# Controller.net
KiCad netlist of a schematic drawn in Altium Designer
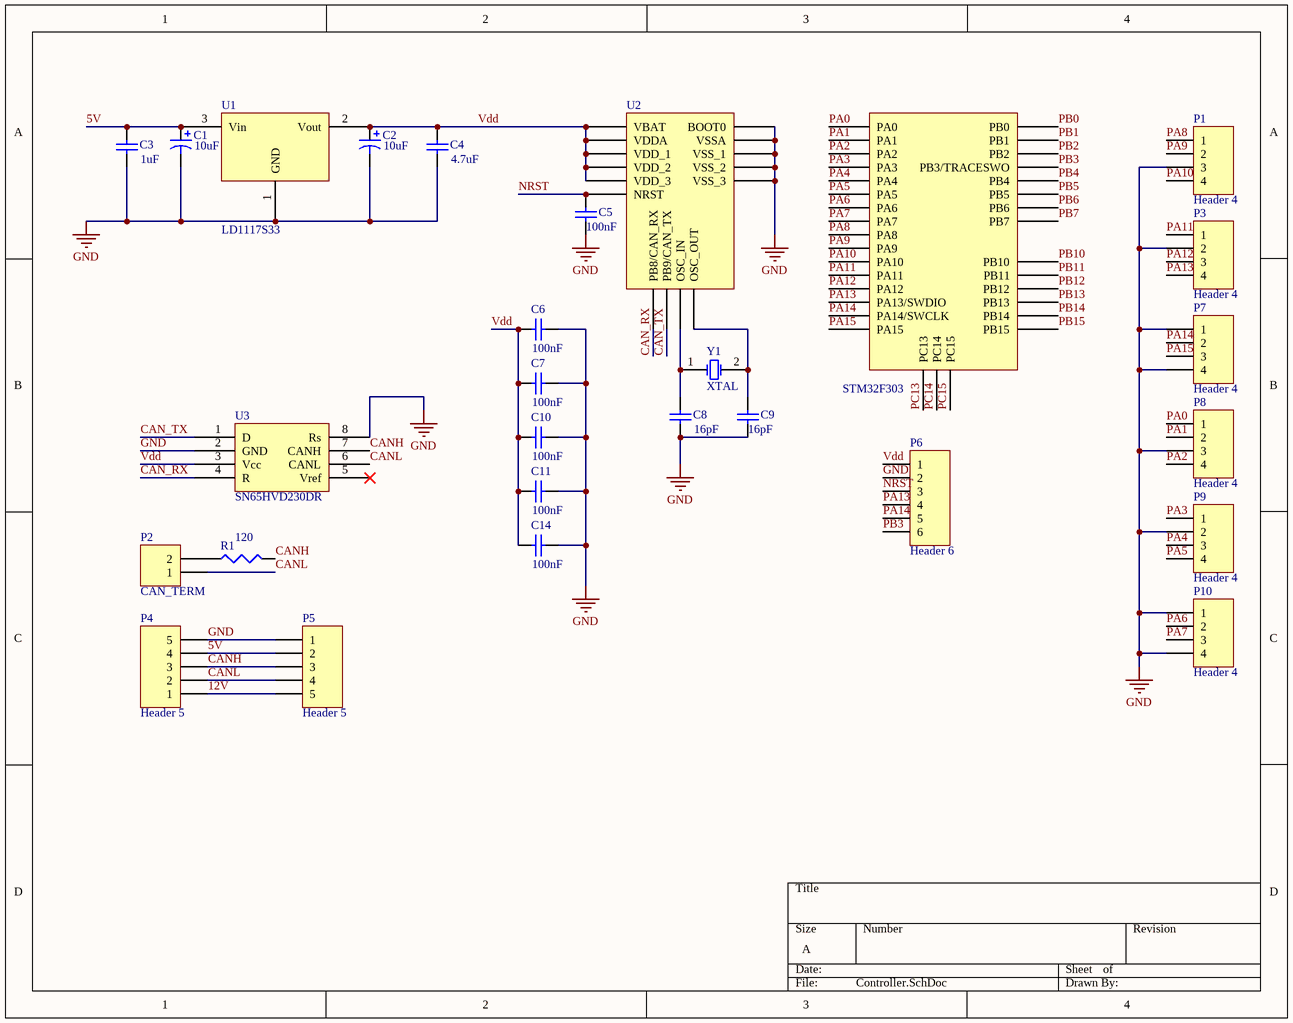
[diagram p0: Controller.SchDoc]

(export (version "E")
  (design (tool "Eeschema 10.0.6"))
  (components
    (comp (ref "C1")
      (value "10uF")
      (footprint "CAPM6032X28N")
      (description "Polarized Capacitor (Surface Mount)")
      (fields (field (name "Comment") "Cap Pol3") (field (name "PUBLISHER") "Altium Limited"))
      (libsource (lib "Miscellaneous Devices") (part "Cap Pol3"))
    )
    (comp (ref "C2")
      (value "10uF")
      (footprint "CAPM6032X28N")
      (description "Polarized Capacitor (Surface Mount)")
      (fields (field (name "Comment") "Cap Pol3") (field (name "PUBLISHER") "Altium Limited"))
      (libsource (lib "Miscellaneous Devices") (part "Cap Pol3"))
    )
    (comp (ref "C3")
      (value "1uF")
      (footprint "1608[0603]")
      (description "Capacitor (Semiconductor SIM Model)")
      (fields (field (name "Comment") "Cap Semi") (field (name "PUBLISHER") "Altium Limited"))
      (libsource (lib "Miscellaneous Devices") (part "Cap Semi"))
    )
    (comp (ref "C4")
      (value "4.7uF")
      (footprint "1608[0603]")
      (description "Capacitor (Semiconductor SIM Model)")
      (fields (field (name "Comment") "Cap Semi") (field (name "PUBLISHER") "Altium Limited"))
      (libsource (lib "Miscellaneous Devices") (part "Cap Semi"))
    )
    (comp (ref "C5")
      (value "100nF")
      (footprint "1608[0603]")
      (description "Capacitor (Semiconductor SIM Model)")
      (fields (field (name "Comment") "Cap Semi") (field (name "PUBLISHER") "Altium Limited"))
      (libsource (lib "Miscellaneous Devices") (part "Cap Semi"))
    )
    (comp (ref "C6")
      (value "100nF")
      (footprint "1608[0603]")
      (description "Capacitor (Semiconductor SIM Model)")
      (fields (field (name "Comment") "Cap Semi") (field (name "PUBLISHER") "Altium Limited"))
      (libsource (lib "Miscellaneous Devices") (part "Cap Semi"))
    )
    (comp (ref "C7")
      (value "100nF")
      (footprint "1608[0603]")
      (description "Capacitor (Semiconductor SIM Model)")
      (fields (field (name "Comment") "Cap Semi") (field (name "PUBLISHER") "Altium Limited"))
      (libsource (lib "Miscellaneous Devices") (part "Cap Semi"))
    )
    (comp (ref "C8")
      (value "16pF")
      (footprint "1608[0603]")
      (description "Capacitor (Semiconductor SIM Model)")
      (fields (field (name "Comment") "Cap Semi") (field (name "PUBLISHER") "Altium Limited"))
      (libsource (lib "Miscellaneous Devices") (part "Cap Semi"))
    )
    (comp (ref "C9")
      (value "16pF")
      (footprint "1608[0603]")
      (description "Capacitor (Semiconductor SIM Model)")
      (fields (field (name "Comment") "Cap Semi") (field (name "PUBLISHER") "Altium Limited"))
      (libsource (lib "Miscellaneous Devices") (part "Cap Semi"))
    )
    (comp (ref "C10")
      (value "100nF")
      (footprint "1608[0603]")
      (description "Capacitor (Semiconductor SIM Model)")
      (fields (field (name "Comment") "Cap Semi") (field (name "PUBLISHER") "Altium Limited"))
      (libsource (lib "Miscellaneous Devices") (part "Cap Semi"))
    )
    (comp (ref "C11")
      (value "100nF")
      (footprint "1608[0603]")
      (description "Capacitor (Semiconductor SIM Model)")
      (fields (field (name "Comment") "Cap Semi") (field (name "PUBLISHER") "Altium Limited"))
      (libsource (lib "Miscellaneous Devices") (part "Cap Semi"))
    )
    (comp (ref "C14")
      (value "100nF")
      (footprint "1608[0603]")
      (description "Capacitor (Semiconductor SIM Model)")
      (fields (field (name "Comment") "Cap Semi") (field (name "PUBLISHER") "Altium Limited"))
      (libsource (lib "Miscellaneous Devices") (part "Cap Semi"))
    )
    (comp (ref "P1")
      (value "Header 4")
      (footprint "PH_CONN_4")
      (description "Header, 4-Pin")
      (fields (field (name "PUBLISHER") "Altium Limited"))
      (libsource (lib "Miscellaneous Connectors") (part "Header 4"))
    )
    (comp (ref "P2")
      (value "CAN_TERM")
      (footprint "HDR1X2")
      (description "Header, 2-Pin")
      (fields (field (name "PUBLISHER") "Altium Limited"))
      (libsource (lib "Miscellaneous Connectors") (part "Header 2"))
    )
    (comp (ref "P3")
      (value "Header 4")
      (footprint "PH_CONN_4")
      (description "Header, 4-Pin")
      (fields (field (name "PUBLISHER") "Altium Limited"))
      (libsource (lib "Miscellaneous Connectors") (part "Header 4"))
    )
    (comp (ref "P4")
      (value "Header 5")
      (footprint "CONN_5")
      (description "Header, 5-Pin")
      (fields (field (name "PUBLISHER") "Altium Limited"))
      (libsource (lib "") (part "Header 5_1"))
    )
    (comp (ref "P5")
      (value "Header 5")
      (footprint "CONN_5")
      (description "Header, 5-Pin")
      (fields (field (name "PUBLISHER") "Altium Limited"))
      (libsource (lib "Miscellaneous Connectors") (part "Header 5"))
    )
    (comp (ref "P6")
      (value "Header 6")
      (footprint "HDR2X3")
      (description "Header, 6-Pin")
      (fields (field (name "PUBLISHER") "Altium Limited"))
      (libsource (lib "Miscellaneous Connectors") (part "Header 6"))
    )
    (comp (ref "P7")
      (value "Header 4")
      (footprint "PH_CONN_4")
      (description "Header, 4-Pin")
      (fields (field (name "PUBLISHER") "Altium Limited"))
      (libsource (lib "Miscellaneous Connectors") (part "Header 4"))
    )
    (comp (ref "P8")
      (value "Header 4")
      (footprint "PH_CONN_4")
      (description "Header, 4-Pin")
      (fields (field (name "PUBLISHER") "Altium Limited"))
      (libsource (lib "Miscellaneous Connectors") (part "Header 4"))
    )
    (comp (ref "P9")
      (value "Header 4")
      (footprint "PH_CONN_4")
      (description "Header, 4-Pin")
      (fields (field (name "PUBLISHER") "Altium Limited"))
      (libsource (lib "Miscellaneous Connectors") (part "Header 4"))
    )
    (comp (ref "P10")
      (value "Header 4")
      (footprint "PH_CONN_4")
      (description "Header, 4-Pin")
      (fields (field (name "PUBLISHER") "Altium Limited"))
      (libsource (lib "Miscellaneous Connectors") (part "Header 4"))
    )
    (comp (ref "R1")
      (value "120")
      (footprint "RESC5025X07N")
      (description "Resistor")
      (fields (field (name "Comment") "Res3") (field (name "PUBLISHER") "Altium Limited"))
      (libsource (lib "Miscellaneous Devices") (part "Res3"))
    )
    (comp (ref "U1")
      (value "LD1117S33")
      (footprint "SOT230P700X180-4N")
      (libsource (lib "SoporokoHost") (part "LD1117S33"))
    )
    (comp (ref "U2")
      (value "STM32F303")
      (footprint "TSQFP50P900X900X160-48N")
      (libsource (lib "SoporokoHost") (part "STM32F303"))
    )
    (comp (ref "U3")
      (value "SN65HVD230DR")
      (footprint "SOIC127P600X175-8N")
      (libsource (lib "SoporokoHost") (part "SN65HVD230DR"))
    )
    (comp (ref "Y1")
      (value "XTAL")
      (footprint "HC49/US")
      (description "Crystal Oscillator")
      (fields (field (name "PUBLISHER") "Altium Limited"))
      (libsource (lib "Miscellaneous Devices") (part "XTAL"))
    )
  )
  (nets
    (net (code "1") (name "/5V") (class "Default")
      (node (ref "C1") (pin "1") (pinfunction "1_1") (pintype "passive"))
      (node (ref "C3") (pin "2") (pinfunction "2_2") (pintype "passive"))
      (node (ref "P4") (pin "4") (pinfunction "4_4") (pintype "passive"))
      (node (ref "P5") (pin "2") (pinfunction "2_2") (pintype "passive"))
      (node (ref "U1") (pin "3") (pinfunction "Vin_3") (pintype "passive"))
    )
    (net (code "2") (name "/12V") (class "Default")
      (node (ref "P4") (pin "1") (pinfunction "1_1") (pintype "passive"))
      (node (ref "P5") (pin "5") (pinfunction "5_5") (pintype "passive"))
    )
    (net (code "3") (name "/CANH") (class "Default")
      (node (ref "P4") (pin "3") (pinfunction "3_3") (pintype "passive"))
      (node (ref "P5") (pin "3") (pinfunction "3_3") (pintype "passive"))
      (node (ref "R1") (pin "2") (pinfunction "2_2") (pintype "passive"))
      (node (ref "U3") (pin "7") (pinfunction "CANH_7") (pintype "passive"))
    )
    (net (code "4") (name "/CANL") (class "Default")
      (node (ref "P2") (pin "1") (pinfunction "1_1") (pintype "passive"))
      (node (ref "P4") (pin "2") (pinfunction "2_2") (pintype "passive"))
      (node (ref "P5") (pin "4") (pinfunction "4_4") (pintype "passive"))
      (node (ref "U3") (pin "6") (pinfunction "CANL_6") (pintype "passive"))
    )
    (net (code "5") (name "/CAN_RX") (class "Default")
      (node (ref "U2") (pin "45") (pinfunction "PB8/CAN_RX_45") (pintype "passive"))
      (node (ref "U3") (pin "4") (pinfunction "R_4") (pintype "passive"))
    )
    (net (code "6") (name "/CAN_TX") (class "Default")
      (node (ref "U2") (pin "46") (pinfunction "PB9/CAN_TX_46") (pintype "passive"))
      (node (ref "U3") (pin "1") (pinfunction "D_1") (pintype "passive"))
    )
    (net (code "7") (name "/NRST") (class "Default")
      (node (ref "C5") (pin "1") (pinfunction "1_1") (pintype "passive"))
      (node (ref "P6") (pin "3") (pinfunction "3_3") (pintype "passive"))
      (node (ref "U2") (pin "7") (pinfunction "NRST_7") (pintype "passive"))
    )
    (net (code "8") (name "/PA0") (class "Default")
      (node (ref "P8") (pin "1") (pinfunction "1_1") (pintype "passive"))
      (node (ref "U2") (pin "10") (pinfunction "PA0_10") (pintype "passive"))
    )
    (net (code "9") (name "/PA1") (class "Default")
      (node (ref "P8") (pin "2") (pinfunction "2_2") (pintype "passive"))
      (node (ref "U2") (pin "11") (pinfunction "PA1_11") (pintype "passive"))
    )
    (net (code "10") (name "/PA2") (class "Default")
      (node (ref "P8") (pin "4") (pinfunction "4_4") (pintype "passive"))
      (node (ref "U2") (pin "12") (pinfunction "PA2_12") (pintype "passive"))
    )
    (net (code "11") (name "/PA3") (class "Default")
      (node (ref "P9") (pin "1") (pinfunction "1_1") (pintype "passive"))
      (node (ref "U2") (pin "13") (pinfunction "PA3_13") (pintype "passive"))
    )
    (net (code "12") (name "/PA4") (class "Default")
      (node (ref "P9") (pin "3") (pinfunction "3_3") (pintype "passive"))
      (node (ref "U2") (pin "14") (pinfunction "PA4_14") (pintype "passive"))
    )
    (net (code "13") (name "/PA5") (class "Default")
      (node (ref "P9") (pin "4") (pinfunction "4_4") (pintype "passive"))
      (node (ref "U2") (pin "15") (pinfunction "PA5_15") (pintype "passive"))
    )
    (net (code "14") (name "/PA6") (class "Default")
      (node (ref "P10") (pin "2") (pinfunction "2_2") (pintype "passive"))
      (node (ref "U2") (pin "16") (pinfunction "PA6_16") (pintype "passive"))
    )
    (net (code "15") (name "/PA7") (class "Default")
      (node (ref "P10") (pin "3") (pinfunction "3_3") (pintype "passive"))
      (node (ref "U2") (pin "17") (pinfunction "PA7_17") (pintype "passive"))
    )
    (net (code "16") (name "/PA8") (class "Default")
      (node (ref "P1") (pin "1") (pinfunction "1_1") (pintype "passive"))
      (node (ref "U2") (pin "29") (pinfunction "PA8_29") (pintype "passive"))
    )
    (net (code "17") (name "/PA9") (class "Default")
      (node (ref "P1") (pin "2") (pinfunction "2_2") (pintype "passive"))
      (node (ref "U2") (pin "30") (pinfunction "PA9_30") (pintype "passive"))
    )
    (net (code "18") (name "/PA10") (class "Default")
      (node (ref "P1") (pin "4") (pinfunction "4_4") (pintype "passive"))
      (node (ref "U2") (pin "31") (pinfunction "PA10_31") (pintype "passive"))
    )
    (net (code "19") (name "/PA11") (class "Default")
      (node (ref "P3") (pin "1") (pinfunction "1_1") (pintype "passive"))
      (node (ref "U2") (pin "32") (pinfunction "PA11_32") (pintype "passive"))
    )
    (net (code "20") (name "/PA12") (class "Default")
      (node (ref "P3") (pin "3") (pinfunction "3_3") (pintype "passive"))
      (node (ref "U2") (pin "33") (pinfunction "PA12_33") (pintype "passive"))
    )
    (net (code "21") (name "/PA13") (class "Default")
      (node (ref "P3") (pin "4") (pinfunction "4_4") (pintype "passive"))
      (node (ref "P6") (pin "4") (pinfunction "4_4") (pintype "passive"))
      (node (ref "U2") (pin "34") (pinfunction "PA13/SWDIO_34") (pintype "passive"))
    )
    (net (code "22") (name "/PA14") (class "Default")
      (node (ref "P6") (pin "5") (pinfunction "5_5") (pintype "passive"))
      (node (ref "P7") (pin "2") (pinfunction "2_2") (pintype "passive"))
      (node (ref "U2") (pin "37") (pinfunction "PA14/SWCLK_37") (pintype "passive"))
    )
    (net (code "23") (name "/PA15") (class "Default")
      (node (ref "P7") (pin "3") (pinfunction "3_3") (pintype "passive"))
      (node (ref "U2") (pin "38") (pinfunction "PA15_38") (pintype "passive"))
    )
    (net (code "24") (name "/PB0") (class "Default")
      (node (ref "U2") (pin "18") (pinfunction "PB0_18") (pintype "passive"))
    )
    (net (code "25") (name "/PB1") (class "Default")
      (node (ref "U2") (pin "19") (pinfunction "PB1_19") (pintype "passive"))
    )
    (net (code "26") (name "/PB2") (class "Default")
      (node (ref "U2") (pin "20") (pinfunction "PB2_20") (pintype "passive"))
    )
    (net (code "27") (name "/PB3") (class "Default")
      (node (ref "P6") (pin "6") (pinfunction "6_6") (pintype "passive"))
      (node (ref "U2") (pin "39") (pinfunction "PB3/TRACESWO_39") (pintype "passive"))
    )
    (net (code "28") (name "/PB4") (class "Default")
      (node (ref "U2") (pin "40") (pinfunction "PB4_40") (pintype "passive"))
    )
    (net (code "29") (name "/PB5") (class "Default")
      (node (ref "U2") (pin "41") (pinfunction "PB5_41") (pintype "passive"))
    )
    (net (code "30") (name "/PB6") (class "Default")
      (node (ref "U2") (pin "42") (pinfunction "PB6_42") (pintype "passive"))
    )
    (net (code "31") (name "/PB7") (class "Default")
      (node (ref "U2") (pin "43") (pinfunction "PB7_43") (pintype "passive"))
    )
    (net (code "32") (name "/PB10") (class "Default")
      (node (ref "U2") (pin "21") (pinfunction "PB10_21") (pintype "passive"))
    )
    (net (code "33") (name "/PB11") (class "Default")
      (node (ref "U2") (pin "22") (pinfunction "PB11_22") (pintype "passive"))
    )
    (net (code "34") (name "/PB12") (class "Default")
      (node (ref "U2") (pin "25") (pinfunction "PB12_25") (pintype "passive"))
    )
    (net (code "35") (name "/PB13") (class "Default")
      (node (ref "U2") (pin "26") (pinfunction "PB13_26") (pintype "passive"))
    )
    (net (code "36") (name "/PB14") (class "Default")
      (node (ref "U2") (pin "27") (pinfunction "PB14_27") (pintype "passive"))
    )
    (net (code "37") (name "/PB15") (class "Default")
      (node (ref "U2") (pin "28") (pinfunction "PB15_28") (pintype "passive"))
    )
    (net (code "38") (name "/PC13") (class "Default")
      (node (ref "U2") (pin "2") (pinfunction "PC13_2") (pintype "passive"))
    )
    (net (code "39") (name "/PC14") (class "Default")
      (node (ref "U2") (pin "3") (pinfunction "PC14_3") (pintype "passive"))
    )
    (net (code "40") (name "/PC15") (class "Default")
      (node (ref "U2") (pin "4") (pinfunction "PC15_4") (pintype "passive"))
    )
    (net (code "41") (name "/Vdd") (class "Default")
      (node (ref "C10") (pin "2") (pinfunction "2_2") (pintype "passive"))
      (node (ref "C11") (pin "2") (pinfunction "2_2") (pintype "passive"))
      (node (ref "C14") (pin "2") (pinfunction "2_2") (pintype "passive"))
      (node (ref "C2") (pin "1") (pinfunction "1_1") (pintype "passive"))
      (node (ref "C4") (pin "2") (pinfunction "2_2") (pintype "passive"))
      (node (ref "C6") (pin "2") (pinfunction "2_2") (pintype "passive"))
      (node (ref "C7") (pin "2") (pinfunction "2_2") (pintype "passive"))
      (node (ref "P6") (pin "1") (pinfunction "1_1") (pintype "passive"))
      (node (ref "U1") (pin "2") (pinfunction "Vout_2") (pintype "passive"))
      (node (ref "U2") (pin "1") (pinfunction "VBAT_1") (pintype "passive"))
      (node (ref "U2") (pin "24") (pinfunction "VDD_2_24") (pintype "passive"))
      (node (ref "U2") (pin "36") (pinfunction "VDD_3_36") (pintype "passive"))
      (node (ref "U2") (pin "48") (pinfunction "VDD_1_48") (pintype "passive"))
      (node (ref "U2") (pin "9") (pinfunction "VDDA_9") (pintype "passive"))
      (node (ref "U3") (pin "3") (pinfunction "Vcc_3") (pintype "passive"))
    )
    (net (code "42") (name "GND") (class "Default")
      (node (ref "C1") (pin "2") (pinfunction "2_2") (pintype "passive"))
      (node (ref "C10") (pin "1") (pinfunction "1_1") (pintype "passive"))
      (node (ref "C11") (pin "1") (pinfunction "1_1") (pintype "passive"))
      (node (ref "C14") (pin "1") (pinfunction "1_1") (pintype "passive"))
      (node (ref "C2") (pin "2") (pinfunction "2_2") (pintype "passive"))
      (node (ref "C3") (pin "1") (pinfunction "1_1") (pintype "passive"))
      (node (ref "C4") (pin "1") (pinfunction "1_1") (pintype "passive"))
      (node (ref "C5") (pin "2") (pinfunction "2_2") (pintype "passive"))
      (node (ref "C6") (pin "1") (pinfunction "1_1") (pintype "passive"))
      (node (ref "C7") (pin "1") (pinfunction "1_1") (pintype "passive"))
      (node (ref "C8") (pin "1") (pinfunction "1_1") (pintype "passive"))
      (node (ref "C9") (pin "1") (pinfunction "1_1") (pintype "passive"))
      (node (ref "P1") (pin "3") (pinfunction "3_3") (pintype "passive"))
      (node (ref "P10") (pin "1") (pinfunction "1_1") (pintype "passive"))
      (node (ref "P10") (pin "4") (pinfunction "4_4") (pintype "passive"))
      (node (ref "P3") (pin "2") (pinfunction "2_2") (pintype "passive"))
      (node (ref "P4") (pin "5") (pinfunction "5_5") (pintype "passive"))
      (node (ref "P5") (pin "1") (pinfunction "1_1") (pintype "passive"))
      (node (ref "P6") (pin "2") (pinfunction "2_2") (pintype "passive"))
      (node (ref "P7") (pin "1") (pinfunction "1_1") (pintype "passive"))
      (node (ref "P7") (pin "4") (pinfunction "4_4") (pintype "passive"))
      (node (ref "P8") (pin "3") (pinfunction "3_3") (pintype "passive"))
      (node (ref "P9") (pin "2") (pinfunction "2_2") (pintype "passive"))
      (node (ref "U1") (pin "1") (pinfunction "GND_1") (pintype "passive"))
      (node (ref "U2") (pin "23") (pinfunction "VSS_2_23") (pintype "passive"))
      (node (ref "U2") (pin "35") (pinfunction "VSS_3_35") (pintype "passive"))
      (node (ref "U2") (pin "44") (pinfunction "BOOT0_44") (pintype "passive"))
      (node (ref "U2") (pin "47") (pinfunction "VSS_1_47") (pintype "passive"))
      (node (ref "U2") (pin "8") (pinfunction "VSSA_8") (pintype "passive"))
      (node (ref "U3") (pin "2") (pinfunction "GND_2") (pintype "passive"))
      (node (ref "U3") (pin "8") (pinfunction "Rs_8") (pintype "passive"))
    )
    (net (code "43") (name "Net-(P2-Pad2)") (class "Default")
      (node (ref "P2") (pin "2") (pinfunction "2_2") (pintype "passive"))
      (node (ref "R1") (pin "1") (pinfunction "1_1") (pintype "passive"))
    )
    (net (code "44") (name "Net-(U2-OSC_IN)") (class "Default")
      (node (ref "C8") (pin "2") (pinfunction "2_2") (pintype "passive"))
      (node (ref "U2") (pin "5") (pinfunction "OSC_IN_5") (pintype "passive"))
      (node (ref "Y1") (pin "1") (pinfunction "OSC1_1") (pintype "passive"))
    )
    (net (code "45") (name "Net-(U2-OSC_OUT)") (class "Default")
      (node (ref "C9") (pin "2") (pinfunction "2_2") (pintype "passive"))
      (node (ref "U2") (pin "6") (pinfunction "OSC_OUT_6") (pintype "passive"))
      (node (ref "Y1") (pin "2") (pinfunction "OSC2_2") (pintype "passive"))
    )
    (net (code "46") (name "unconnected-(U3-Vref-Pad5)") (class "Default")
      (node (ref "U3") (pin "5") (pinfunction "Vref_5") (pintype "passive+no_connect"))
    )
  )
)
